# EXT_U_DET.net
KiCad netlist of a schematic drawn in Altium Designer
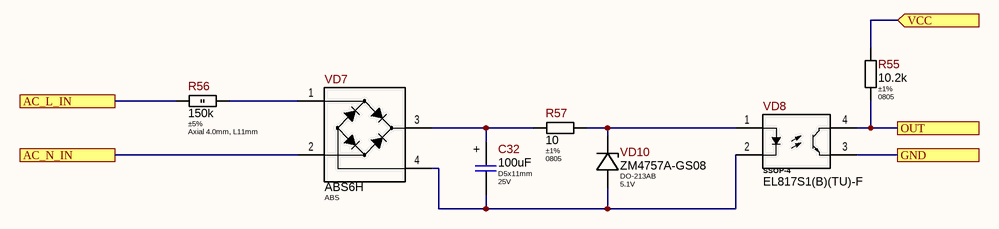
[diagram p0: EXT_U_DET.SchDoc]

(export (version "E")
  (design (tool "Eeschema 10.0.6"))
  (components
    (comp (ref "C32")
      (value "100uF")
      (footprint "CAP-AE-PTH-50D05x110H15")
      (description "100uF 25V ±20% D5x11mm 105℃ Aluminum Electrolytic Capacitor")
      (fields
        (field (name "PACKAGE") "D5x11mm")
        (field (name "VOLTAGE") "25V")
        (field (name "PART NUMBER") "KRM-025V101MC110-T/A2")
        (field (name "MANUFACTURER") "Koshin")
      )
      (libsource (lib "capacitors") (part "KRM-025V101MC110-T/A2"))
    )
    (comp (ref "R55")
      (value "10.2k")
      (footprint "R_ANY_CHIP_0805_MED")
      (description "10.2 kOhms ±1%, 1/8W 0805 Thick Film Resistor")
      (fields
        (field (name "TOLERANCE") "±1%")
        (field (name "PACKAGE") "0805")
        (field (name "PART NUMBER") "RC0805FR-0710K2L")
        (field (name "MANUFACTURER") "Yageo")
      )
      (libsource (lib "resistors") (part "RC0805FR-0710K2L"))
    )
    (comp (ref "R56")
      (value "150k")
      (footprint "MOR200S-Series")
      (description "150k Ohm ±5%, 2W d4.0mm L11mm Axial Through Hole, Metal Oxide Resistor, Al2O3")
      (fields
        (field (name "TOLERANCE") "±5%")
        (field (name "PACKAGE") "Axial 4.0mm, L11mm")
        (field (name "PART NUMBER") "MOR200SJTB-10R")
        (field (name "MANUFACTURER") "Hitano")
      )
      (libsource (lib "resistors") (part "MOR200SJTB-10R"))
    )
    (comp (ref "R57")
      (value "10")
      (footprint "R_ANY_CHIP_0805_MED")
      (description "10 Ohms ±1%, 1/8W 0805 Thick Film Resistor")
      (fields
        (field (name "TOLERANCE") "±1%")
        (field (name "PACKAGE") "0805")
        (field (name "PART NUMBER") "RC0805FR-0710RL")
        (field (name "MANUFACTURER") "Yageo")
      )
      (libsource (lib "resistors") (part "RC0805FR-0710RL"))
    )
    (comp (ref "VD7")
      (value "ABS6H")
      (footprint "ABSxx-Series")
      (description "1A, 600V Standard Bridge Rectifier, ABS Package")
      (fields
        (field (name "PART NUMBER") "ABS6H")
        (field (name "PACKAGE") "ABS")
        (field (name "MANUFACTURER") "Taiwan Semiconductor")
        (field (name "VOLTAGE") "600V")
      )
      (libsource (lib "diodes") (part "ABS6H"))
    )
    (comp (ref "VD8")
      (value "EL817S1(B)(TU)-F")
      (footprint "EL-817S1-(x)(xx)")
      (description "1-Channel Photocoupler, 5kV, 130-260% CTR, SSOP-4")
      (fields
        (field (name "PACKAGE") "SSOP-4")
        (field (name "PART NUMBER") "EL817S1(B)(TU)-F")
        (field (name "MANUFACTURER") "Everlight Electronics")
      )
      (libsource (lib "opto") (part "EL817S1(B)(TU)-F"))
    )
    (comp (ref "VD10")
      (value "ZM4757A-GS08")
      (footprint "DO-213AB")
      (description "Zener Diode 5.1V, 1W, ±5%, 5uA Reverse Current, DO-213AB")
      (fields
        (field (name "PART NUMBER") "ZM4757A-GS08")
        (field (name "PACKAGE") "DO-213AB")
        (field (name "VOLTAGE") "5.1V")
        (field (name "MANUFACTURER") "Vishay Semiconductor")
      )
      (libsource (lib "diodes") (part "ZM4757A-GS08"))
    )
  )
  (nets
    (net (code "1") (name "/AC_L_IN") (class "Default") (node (ref "R56") (pin "1") (pintype "passive")))
    (net (code "2") (name "/AC_N_IN") (class "Default")
      (node (ref "VD7") (pin "2") (pinfunction "~_2") (pintype "passive"))
    )
    (net (code "3") (name "/GND") (class "Default")
      (node (ref "VD8") (pin "3") (pinfunction "Emitter_3") (pintype "passive"))
    )
    (net (code "4") (name "/OUT") (class "Default")
      (node (ref "R55") (pin "2") (pintype "passive"))
      (node (ref "VD8") (pin "4") (pinfunction "Collector_4") (pintype "passive"))
    )
    (net (code "5") (name "/VCC") (class "Default") (node (ref "R55") (pin "1") (pintype "passive")))
    (net (code "6") (name "Net-(R56-Pad2)") (class "Default")
      (node (ref "R56") (pin "2") (pintype "passive"))
      (node (ref "VD7") (pin "1") (pinfunction "~_1") (pintype "passive"))
    )
    (net (code "7") (name "Net-(VD7-+)") (class "Default")
      (node (ref "C32") (pin "1") (pinfunction "1_1") (pintype "passive"))
      (node (ref "R57") (pin "1") (pintype "passive"))
      (node (ref "VD7") (pin "3") (pinfunction "+_3") (pintype "passive"))
    )
    (net (code "8") (name "Net-(VD7--)") (class "Default")
      (node (ref "C32") (pin "2") (pinfunction "2_2") (pintype "passive"))
      (node (ref "VD10") (pin "AN") (pintype "passive"))
      (node (ref "VD7") (pin "4") (pinfunction "-_4") (pintype "passive"))
      (node (ref "VD8") (pin "2") (pinfunction "Cathode_2") (pintype "passive"))
    )
    (net (code "9") (name "Net-(VD8-Anode)") (class "Default")
      (node (ref "R57") (pin "2") (pintype "passive"))
      (node (ref "VD10") (pin "CA") (pintype "passive"))
      (node (ref "VD8") (pin "1") (pinfunction "Anode_1") (pintype "passive"))
    )
  )
)
